# E49400T20S.net
KiCad netlist of a schematic drawn in Altium Designer
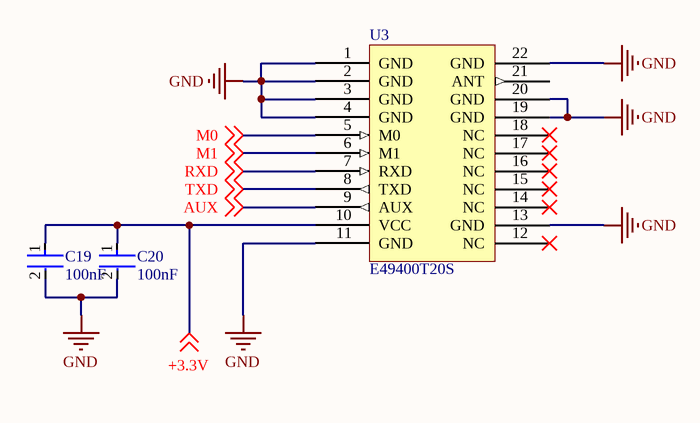
[diagram p0: E49400T20S.SchDoc]

(export (version "E")
  (design (tool "Eeschema 10.0.6"))
  (components
    (comp (ref "C19")
      (value "100nF")
      (footprint "FP-CGA3E-0_3-0_1-IPC_A")
      (description "Cap Ceramic 100nF 50V X7R 10% Pad SMD 0603 +125°C Automotive T/R")
      (fields (field (name "TOLERANCE") "10%") (field (name "VOLTAGE") "50V"))
      (libsource (lib "Altium Content Vault") (part "b4654b650e69147ec39a6b967a45e02"))
    )
    (comp (ref "C20")
      (value "100nF")
      (footprint "FP-CGA3E-0_3-0_1-IPC_A")
      (description "Cap Ceramic 100nF 50V X7R 10% Pad SMD 0603 +125°C Automotive T/R")
      (fields (field (name "TOLERANCE") "10%") (field (name "VOLTAGE") "50V"))
      (libsource (lib "Altium Content Vault") (part "b4654b650e69147ec39a6b967a45e02"))
    )
    (comp (ref "U3")
      (value "E49400T20S")
      (footprint "PCBComponent_1")
      (libsource (lib "E49400T20S") (part "Component_1"))
    )
  )
  (nets
    (net (code "1") (name "+3.3V") (class "Default")
      (node (ref "C19") (pin "1") (pinfunction "1_1") (pintype "passive"))
      (node (ref "C20") (pin "1") (pinfunction "1_1") (pintype "passive"))
      (node (ref "U3") (pin "10") (pinfunction "VCC_10") (pintype "power_in"))
    )
    (net (code "2") (name "AUX") (class "Default")
      (node (ref "U3") (pin "9") (pinfunction "AUX_9") (pintype "output"))
    )
    (net (code "3") (name "GND") (class "Default")
      (node (ref "C19") (pin "2") (pinfunction "2_2") (pintype "passive"))
      (node (ref "C20") (pin "2") (pinfunction "2_2") (pintype "passive"))
      (node (ref "U3") (pin "1") (pinfunction "GND_1") (pintype "passive"))
      (node (ref "U3") (pin "11") (pinfunction "GND_11") (pintype "passive"))
      (node (ref "U3") (pin "13") (pinfunction "GND_13") (pintype "passive"))
      (node (ref "U3") (pin "19") (pinfunction "GND_19") (pintype "passive"))
      (node (ref "U3") (pin "2") (pinfunction "GND_2") (pintype "passive"))
      (node (ref "U3") (pin "20") (pinfunction "GND_20") (pintype "passive"))
      (node (ref "U3") (pin "22") (pinfunction "GND_22") (pintype "passive"))
      (node (ref "U3") (pin "3") (pinfunction "GND_3") (pintype "passive"))
      (node (ref "U3") (pin "4") (pinfunction "GND_4") (pintype "passive"))
    )
    (net (code "4") (name "M0") (class "Default")
      (node (ref "U3") (pin "5") (pinfunction "M0_5") (pintype "input"))
    )
    (net (code "5") (name "M1") (class "Default")
      (node (ref "U3") (pin "6") (pinfunction "M1_6") (pintype "input"))
    )
    (net (code "6") (name "RXD") (class "Default")
      (node (ref "U3") (pin "7") (pinfunction "RXD_7") (pintype "input"))
    )
    (net (code "7") (name "TXD") (class "Default")
      (node (ref "U3") (pin "8") (pinfunction "TXD_8") (pintype "output"))
    )
    (net (code "8") (name "unconnected-(U3-ANT-Pad21)") (class "Default")
      (node (ref "U3") (pin "21") (pinfunction "ANT_21") (pintype "output"))
    )
    (net (code "9") (name "unconnected-(U3-NC-Pad12)") (class "Default")
      (node (ref "U3") (pin "12") (pinfunction "NC_12") (pintype "open_collector+no_connect"))
    )
    (net (code "10") (name "unconnected-(U3-NC-Pad14)") (class "Default")
      (node (ref "U3") (pin "14") (pinfunction "NC_14") (pintype "open_collector+no_connect"))
    )
    (net (code "11") (name "unconnected-(U3-NC-Pad15)") (class "Default")
      (node (ref "U3") (pin "15") (pinfunction "NC_15") (pintype "open_collector+no_connect"))
    )
    (net (code "12") (name "unconnected-(U3-NC-Pad16)") (class "Default")
      (node (ref "U3") (pin "16") (pinfunction "NC_16") (pintype "open_collector+no_connect"))
    )
    (net (code "13") (name "unconnected-(U3-NC-Pad17)") (class "Default")
      (node (ref "U3") (pin "17") (pinfunction "NC_17") (pintype "open_collector+no_connect"))
    )
    (net (code "14") (name "unconnected-(U3-NC-Pad18)") (class "Default")
      (node (ref "U3") (pin "18") (pinfunction "NC_18") (pintype "open_collector+no_connect"))
    )
  )
)
